# jp_2021_3_10.net
KiCad netlist of a schematic drawn in Altium Designer
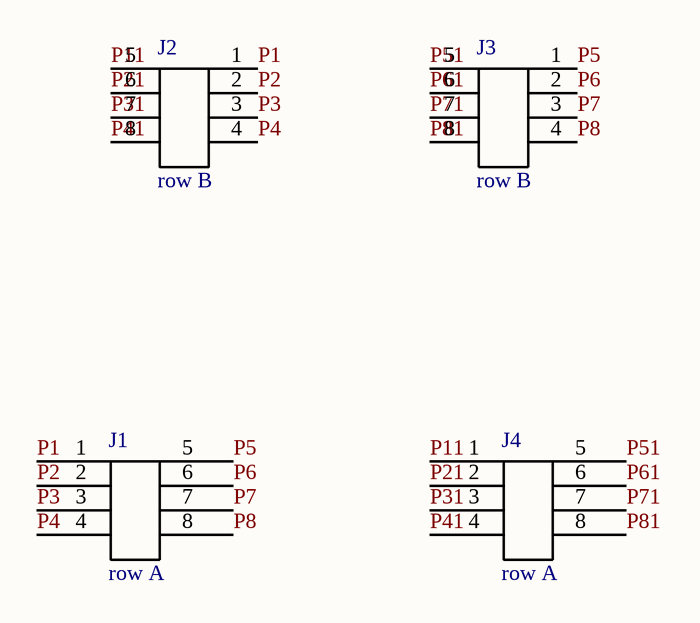
[diagram p0: jp_2021.3.10.SchDoc]

(export (version "E")
  (design (tool "Eeschema 10.0.6"))
  (components
    (comp (ref "J1") (value "row A") (footprint "row A") (libsource (lib "jp_2021.3.10") (part "row A")))
    (comp (ref "J2") (value "row B") (footprint "row B") (libsource (lib "jp_2021.3.10") (part "row B")))
    (comp (ref "J3") (value "row B") (footprint "row B") (libsource (lib "jp_2021.3.10") (part "row B")))
    (comp (ref "J4") (value "row A") (footprint "row A") (libsource (lib "jp_2021.3.10") (part "row A")))
  )
  (nets
    (net (code "1") (name "/P1") (class "Default")
      (node (ref "J1") (pin "1") (pinfunction "12_1") (pintype "passive"))
      (node (ref "J2") (pin "1") (pinfunction "8_1") (pintype "passive"))
    )
    (net (code "2") (name "/P2") (class "Default")
      (node (ref "J1") (pin "2") (pinfunction "13_2") (pintype "passive"))
      (node (ref "J2") (pin "2") (pinfunction "9_2") (pintype "passive"))
    )
    (net (code "3") (name "/P3") (class "Default")
      (node (ref "J1") (pin "3") (pinfunction "14_3") (pintype "passive"))
      (node (ref "J2") (pin "3") (pinfunction "10_3") (pintype "passive"))
    )
    (net (code "4") (name "/P4") (class "Default")
      (node (ref "J1") (pin "4") (pinfunction "15_4") (pintype "passive"))
      (node (ref "J2") (pin "4") (pinfunction "11_4") (pintype "passive"))
    )
    (net (code "5") (name "/P5") (class "Default")
      (node (ref "J1") (pin "5") (pinfunction "8_5") (pintype "passive"))
      (node (ref "J3") (pin "1") (pinfunction "8_1") (pintype "passive"))
    )
    (net (code "6") (name "/P6") (class "Default")
      (node (ref "J1") (pin "6") (pinfunction "9_6") (pintype "passive"))
      (node (ref "J3") (pin "2") (pinfunction "9_2") (pintype "passive"))
    )
    (net (code "7") (name "/P7") (class "Default")
      (node (ref "J1") (pin "7") (pinfunction "10_7") (pintype "passive"))
      (node (ref "J3") (pin "3") (pinfunction "10_3") (pintype "passive"))
    )
    (net (code "8") (name "/P8") (class "Default")
      (node (ref "J1") (pin "8") (pinfunction "11_8") (pintype "passive"))
      (node (ref "J3") (pin "4") (pinfunction "11_4") (pintype "passive"))
    )
    (net (code "9") (name "/P11") (class "Default")
      (node (ref "J2") (pin "5") (pinfunction "5_5") (pintype "passive"))
      (node (ref "J4") (pin "1") (pinfunction "12_1") (pintype "passive"))
    )
    (net (code "10") (name "/P21") (class "Default")
      (node (ref "J2") (pin "6") (pinfunction "6_6") (pintype "passive"))
      (node (ref "J4") (pin "2") (pinfunction "13_2") (pintype "passive"))
    )
    (net (code "11") (name "/P31") (class "Default")
      (node (ref "J2") (pin "7") (pinfunction "7_7") (pintype "passive"))
      (node (ref "J4") (pin "3") (pinfunction "14_3") (pintype "passive"))
    )
    (net (code "12") (name "/P41") (class "Default")
      (node (ref "J2") (pin "8") (pinfunction "8_8") (pintype "passive"))
      (node (ref "J4") (pin "4") (pinfunction "15_4") (pintype "passive"))
    )
    (net (code "13") (name "/P51") (class "Default")
      (node (ref "J3") (pin "5") (pinfunction "5_5") (pintype "passive"))
      (node (ref "J4") (pin "5") (pinfunction "8_5") (pintype "passive"))
    )
    (net (code "14") (name "/P61") (class "Default")
      (node (ref "J3") (pin "6") (pinfunction "6_6") (pintype "passive"))
      (node (ref "J4") (pin "6") (pinfunction "9_6") (pintype "passive"))
    )
    (net (code "15") (name "/P71") (class "Default")
      (node (ref "J3") (pin "7") (pinfunction "7_7") (pintype "passive"))
      (node (ref "J4") (pin "7") (pinfunction "10_7") (pintype "passive"))
    )
    (net (code "16") (name "/P81") (class "Default")
      (node (ref "J3") (pin "8") (pinfunction "8_8") (pintype "passive"))
      (node (ref "J4") (pin "8") (pinfunction "11_8") (pintype "passive"))
    )
  )
)
